# Core_Analogue_Inputs.net
KiCad netlist of a schematic drawn in Altium Designer
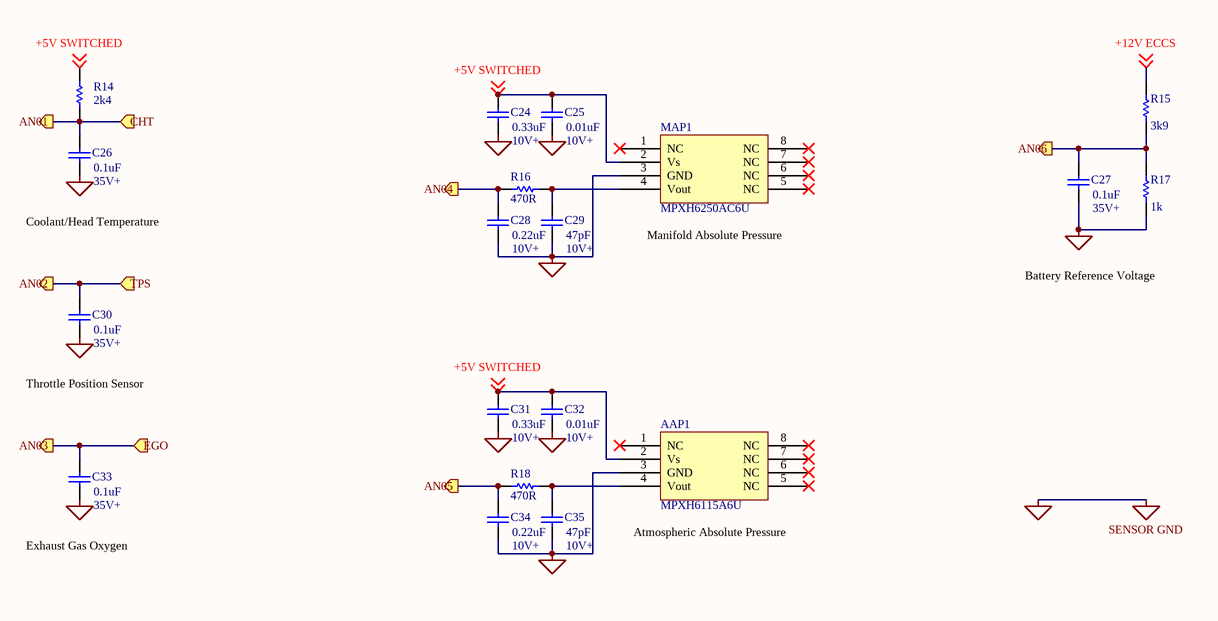
[diagram p0: Core Analogue Inputs.SchDoc]

(export (version "E")
  (design (tool "Eeschema 10.0.6"))
  (components
    (comp (ref "AAP1")
      (value "MPXH6115A6U")
      (libsource (lib "FreeEMS Schematic Library") (part "MPXH6115A6T1"))
    )
    (comp (ref "C24")
      (value "0.33uF")
      (footprint "RAD-0.3")
      (description "Capacitor")
      (fields (field (name "PUBLISHER") "Altium Limited"))
      (libsource (lib "Miscellaneous Devices") (part "Cap"))
    )
    (comp (ref "C25")
      (value "0.01uF")
      (footprint "RAD-0.3")
      (description "Capacitor")
      (fields (field (name "PUBLISHER") "Altium Limited"))
      (libsource (lib "Miscellaneous Devices") (part "Cap"))
    )
    (comp (ref "C26")
      (value "0.1uF")
      (footprint "RAD-0.3")
      (description "Capacitor")
      (fields (field (name "PUBLISHER") "Altium Limited"))
      (libsource (lib "Miscellaneous Devices") (part "Cap"))
    )
    (comp (ref "C27")
      (value "0.1uF")
      (footprint "RAD-0.3")
      (description "Capacitor")
      (fields (field (name "PUBLISHER") "Altium Limited"))
      (libsource (lib "Miscellaneous Devices") (part "Cap"))
    )
    (comp (ref "C28")
      (value "0.22uF")
      (footprint "RAD-0.3")
      (description "Capacitor")
      (fields (field (name "PUBLISHER") "Altium Limited"))
      (libsource (lib "Miscellaneous Devices") (part "Cap"))
    )
    (comp (ref "C29")
      (value "47pF")
      (footprint "RAD-0.3")
      (description "Capacitor")
      (fields (field (name "PUBLISHER") "Altium Limited"))
      (libsource (lib "Miscellaneous Devices") (part "Cap"))
    )
    (comp (ref "C30")
      (value "0.1uF")
      (footprint "RAD-0.3")
      (description "Capacitor")
      (fields (field (name "PUBLISHER") "Altium Limited"))
      (libsource (lib "Miscellaneous Devices") (part "Cap"))
    )
    (comp (ref "C31")
      (value "0.33uF")
      (footprint "RAD-0.3")
      (description "Capacitor")
      (fields (field (name "PUBLISHER") "Altium Limited"))
      (libsource (lib "Miscellaneous Devices") (part "Cap"))
    )
    (comp (ref "C32")
      (value "0.01uF")
      (footprint "RAD-0.3")
      (description "Capacitor")
      (fields (field (name "PUBLISHER") "Altium Limited"))
      (libsource (lib "Miscellaneous Devices") (part "Cap"))
    )
    (comp (ref "C33")
      (value "0.1uF")
      (footprint "RAD-0.3")
      (description "Capacitor")
      (fields (field (name "PUBLISHER") "Altium Limited"))
      (libsource (lib "Miscellaneous Devices") (part "Cap"))
    )
    (comp (ref "C34")
      (value "0.22uF")
      (footprint "RAD-0.3")
      (description "Capacitor")
      (fields (field (name "PUBLISHER") "Altium Limited"))
      (libsource (lib "Miscellaneous Devices") (part "Cap"))
    )
    (comp (ref "C35")
      (value "47pF")
      (footprint "RAD-0.3")
      (description "Capacitor")
      (fields (field (name "PUBLISHER") "Altium Limited"))
      (libsource (lib "Miscellaneous Devices") (part "Cap"))
    )
    (comp (ref "MAP1")
      (value "MPXH6250AC6U")
      (libsource (lib "FreeEMS Schematic Library") (part "MPXH6250AC6U"))
    )
    (comp (ref "R14")
      (value "2k4")
      (footprint "AXIAL-0.3")
      (description "Resistor")
      (fields (field (name "PUBLISHER") "Altium Limited"))
      (libsource (lib "Miscellaneous Devices") (part "Res1"))
    )
    (comp (ref "R15")
      (value "3k9")
      (footprint "AXIAL-0.3")
      (description "Resistor")
      (fields (field (name "PUBLISHER") "Altium Limited"))
      (libsource (lib "Miscellaneous Devices") (part "Res1"))
    )
    (comp (ref "R16")
      (value "470R")
      (footprint "AXIAL-0.3")
      (description "Resistor")
      (fields (field (name "PUBLISHER") "Altium Limited"))
      (libsource (lib "Miscellaneous Devices") (part "Res1"))
    )
    (comp (ref "R17")
      (value "1k")
      (footprint "AXIAL-0.3")
      (description "Resistor")
      (fields (field (name "PUBLISHER") "Altium Limited"))
      (libsource (lib "Miscellaneous Devices") (part "Res1"))
    )
    (comp (ref "R18")
      (value "470R")
      (footprint "AXIAL-0.3")
      (description "Resistor")
      (fields (field (name "PUBLISHER") "Altium Limited"))
      (libsource (lib "Miscellaneous Devices") (part "Res1"))
    )
  )
  (nets
    (net (code "1") (name "+5V SWITCHED") (class "Default")
      (node (ref "AAP1") (pin "2") (pinfunction "Vs_2") (pintype "passive"))
      (node (ref "C24") (pin "2") (pinfunction "2_2") (pintype "passive"))
      (node (ref "C25") (pin "2") (pinfunction "2_2") (pintype "passive"))
      (node (ref "C31") (pin "2") (pinfunction "2_2") (pintype "passive"))
      (node (ref "C32") (pin "2") (pinfunction "2_2") (pintype "passive"))
      (node (ref "MAP1") (pin "2") (pinfunction "Vs_2") (pintype "passive"))
      (node (ref "R14") (pin "1") (pinfunction "1_1") (pintype "passive"))
    )
    (net (code "2") (name "+12V ECCS") (class "Default")
      (node (ref "R15") (pin "2") (pinfunction "2_2") (pintype "passive"))
    )
    (net (code "3") (name "/AN01") (class "Default")
      (node (ref "C26") (pin "2") (pinfunction "2_2") (pintype "passive"))
      (node (ref "R14") (pin "2") (pinfunction "2_2") (pintype "passive"))
    )
    (net (code "4") (name "/AN02") (class "Default")
      (node (ref "C30") (pin "2") (pinfunction "2_2") (pintype "passive"))
    )
    (net (code "5") (name "/AN03") (class "Default")
      (node (ref "C33") (pin "2") (pinfunction "2_2") (pintype "passive"))
    )
    (net (code "6") (name "/AN04") (class "Default")
      (node (ref "C28") (pin "2") (pinfunction "2_2") (pintype "passive"))
      (node (ref "R16") (pin "1") (pinfunction "1_1") (pintype "passive"))
    )
    (net (code "7") (name "/AN05") (class "Default")
      (node (ref "C34") (pin "2") (pinfunction "2_2") (pintype "passive"))
      (node (ref "R18") (pin "1") (pinfunction "1_1") (pintype "passive"))
    )
    (net (code "8") (name "/AN06") (class "Default")
      (node (ref "C27") (pin "2") (pinfunction "2_2") (pintype "passive"))
      (node (ref "R15") (pin "1") (pinfunction "1_1") (pintype "passive"))
      (node (ref "R17") (pin "2") (pinfunction "2_2") (pintype "passive"))
    )
    (net (code "9") (name "<NO NET>") (class "Default")
      (node (ref "AAP1") (pin "3") (pinfunction "GND_3") (pintype "passive"))
      (node (ref "C24") (pin "1") (pinfunction "1_1") (pintype "passive"))
      (node (ref "C25") (pin "1") (pinfunction "1_1") (pintype "passive"))
      (node (ref "C26") (pin "1") (pinfunction "1_1") (pintype "passive"))
      (node (ref "C27") (pin "1") (pinfunction "1_1") (pintype "passive"))
      (node (ref "C28") (pin "1") (pinfunction "1_1") (pintype "passive"))
      (node (ref "C29") (pin "1") (pinfunction "1_1") (pintype "passive"))
      (node (ref "C30") (pin "1") (pinfunction "1_1") (pintype "passive"))
      (node (ref "C31") (pin "1") (pinfunction "1_1") (pintype "passive"))
      (node (ref "C32") (pin "1") (pinfunction "1_1") (pintype "passive"))
      (node (ref "C33") (pin "1") (pinfunction "1_1") (pintype "passive"))
      (node (ref "C34") (pin "1") (pinfunction "1_1") (pintype "passive"))
      (node (ref "C35") (pin "1") (pinfunction "1_1") (pintype "passive"))
      (node (ref "MAP1") (pin "3") (pinfunction "GND_3") (pintype "passive"))
      (node (ref "R17") (pin "1") (pinfunction "1_1") (pintype "passive"))
    )
    (net (code "10") (name "Net-(AAP1-Vout)") (class "Default")
      (node (ref "AAP1") (pin "4") (pinfunction "Vout_4") (pintype "passive"))
      (node (ref "C35") (pin "2") (pinfunction "2_2") (pintype "passive"))
      (node (ref "R18") (pin "2") (pinfunction "2_2") (pintype "passive"))
    )
    (net (code "11") (name "Net-(MAP1-Vout)") (class "Default")
      (node (ref "C29") (pin "2") (pinfunction "2_2") (pintype "passive"))
      (node (ref "MAP1") (pin "4") (pinfunction "Vout_4") (pintype "passive"))
      (node (ref "R16") (pin "2") (pinfunction "2_2") (pintype "passive"))
    )
    (net (code "12") (name "unconnected-(AAP1-NC-Pad1)") (class "Default")
      (node (ref "AAP1") (pin "1") (pinfunction "NC_1") (pintype "passive+no_connect"))
    )
    (net (code "13") (name "unconnected-(AAP1-NC-Pad5)") (class "Default")
      (node (ref "AAP1") (pin "5") (pinfunction "NC_5") (pintype "passive+no_connect"))
    )
    (net (code "14") (name "unconnected-(AAP1-NC-Pad6)") (class "Default")
      (node (ref "AAP1") (pin "6") (pinfunction "NC_6") (pintype "passive+no_connect"))
    )
    (net (code "15") (name "unconnected-(AAP1-NC-Pad7)") (class "Default")
      (node (ref "AAP1") (pin "7") (pinfunction "NC_7") (pintype "passive+no_connect"))
    )
    (net (code "16") (name "unconnected-(AAP1-NC-Pad8)") (class "Default")
      (node (ref "AAP1") (pin "8") (pinfunction "NC_8") (pintype "passive+no_connect"))
    )
    (net (code "17") (name "unconnected-(MAP1-NC-Pad1)") (class "Default")
      (node (ref "MAP1") (pin "1") (pinfunction "NC_1") (pintype "passive+no_connect"))
    )
    (net (code "18") (name "unconnected-(MAP1-NC-Pad5)") (class "Default")
      (node (ref "MAP1") (pin "5") (pinfunction "NC_5") (pintype "passive+no_connect"))
    )
    (net (code "19") (name "unconnected-(MAP1-NC-Pad6)") (class "Default")
      (node (ref "MAP1") (pin "6") (pinfunction "NC_6") (pintype "passive+no_connect"))
    )
    (net (code "20") (name "unconnected-(MAP1-NC-Pad7)") (class "Default")
      (node (ref "MAP1") (pin "7") (pinfunction "NC_7") (pintype "passive+no_connect"))
    )
    (net (code "21") (name "unconnected-(MAP1-NC-Pad8)") (class "Default")
      (node (ref "MAP1") (pin "8") (pinfunction "NC_8") (pintype "passive+no_connect"))
    )
  )
)
